# power.net
KiCad netlist of a schematic drawn in EAGLE
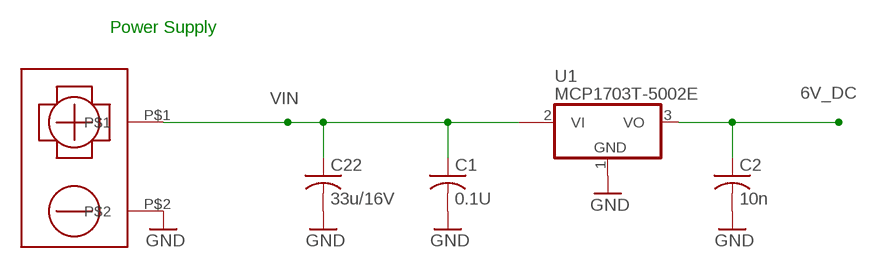
[diagram p0: schematic, sheet 1]

(export (version "E")
  (design (tool "Eeschema 10.0.6"))
  (components
    (comp (ref "C1")
      (value "0.1U")
      (footprint "eagle-import:C0805")
      (libsource (lib "eagle-import") (part "C-USC0805"))
    )
    (comp (ref "C2")
      (value "10n")
      (footprint "eagle-import:C0805")
      (libsource (lib "eagle-import") (part "C-USC0805"))
    )
    (comp (ref "C22")
      (value "33u/16V")
      (footprint "eagle-import:C0805")
      (libsource (lib "eagle-import") (part "C-USC0805"))
    )
    (comp (ref "U$1")
      (value "9V_968")
      (footprint "eagle-import:9V_968")
      (libsource (lib "eagle-import") (part "9V_968"))
    )
    (comp (ref "U1")
      (value "MCP1703T-5002E")
      (footprint "eagle-import:SOT89")
      (libsource (lib "eagle-import") (part "MCP1703MB12"))
    )
  )
  (nets
    (net (code "1") (name "/6V_DC") (class "Default")
      (node (ref "C2") (pin "1") (pinfunction "1_1") (pintype "passive"))
      (node (ref "U1") (pin "3") (pinfunction "VO_3") (pintype "passive"))
    )
    (net (code "2") (name "/VIN") (class "Default")
      (node (ref "C1") (pin "1") (pinfunction "1_1") (pintype "passive"))
      (node (ref "C22") (pin "1") (pinfunction "1_1") (pintype "passive"))
      (node (ref "U$1") (pin "P$1") (pinfunction "P$1_P$1") (pintype "bidirectional"))
      (node (ref "U1") (pin "2@1") (pinfunction "VI1_2@1") (pintype "input"))
    )
    (net (code "3") (name "GND") (class "Default")
      (node (ref "C1") (pin "2") (pinfunction "2_2") (pintype "passive"))
      (node (ref "C2") (pin "2") (pinfunction "2_2") (pintype "passive"))
      (node (ref "C22") (pin "2") (pinfunction "2_2") (pintype "passive"))
      (node (ref "U$1") (pin "P$2") (pinfunction "P$2_P$2") (pintype "bidirectional"))
      (node (ref "U1") (pin "1") (pinfunction "GND_1") (pintype "passive"))
    )
    (net (code "4") (name "unconnected-(U1-VI-Pad2)") (class "Default")
      (node (ref "U1") (pin "2") (pinfunction "VI_2") (pintype "input"))
    )
  )
)
